# Blocky_Mini_Ultra.net
KiCad netlist of a schematic drawn in EAGLE
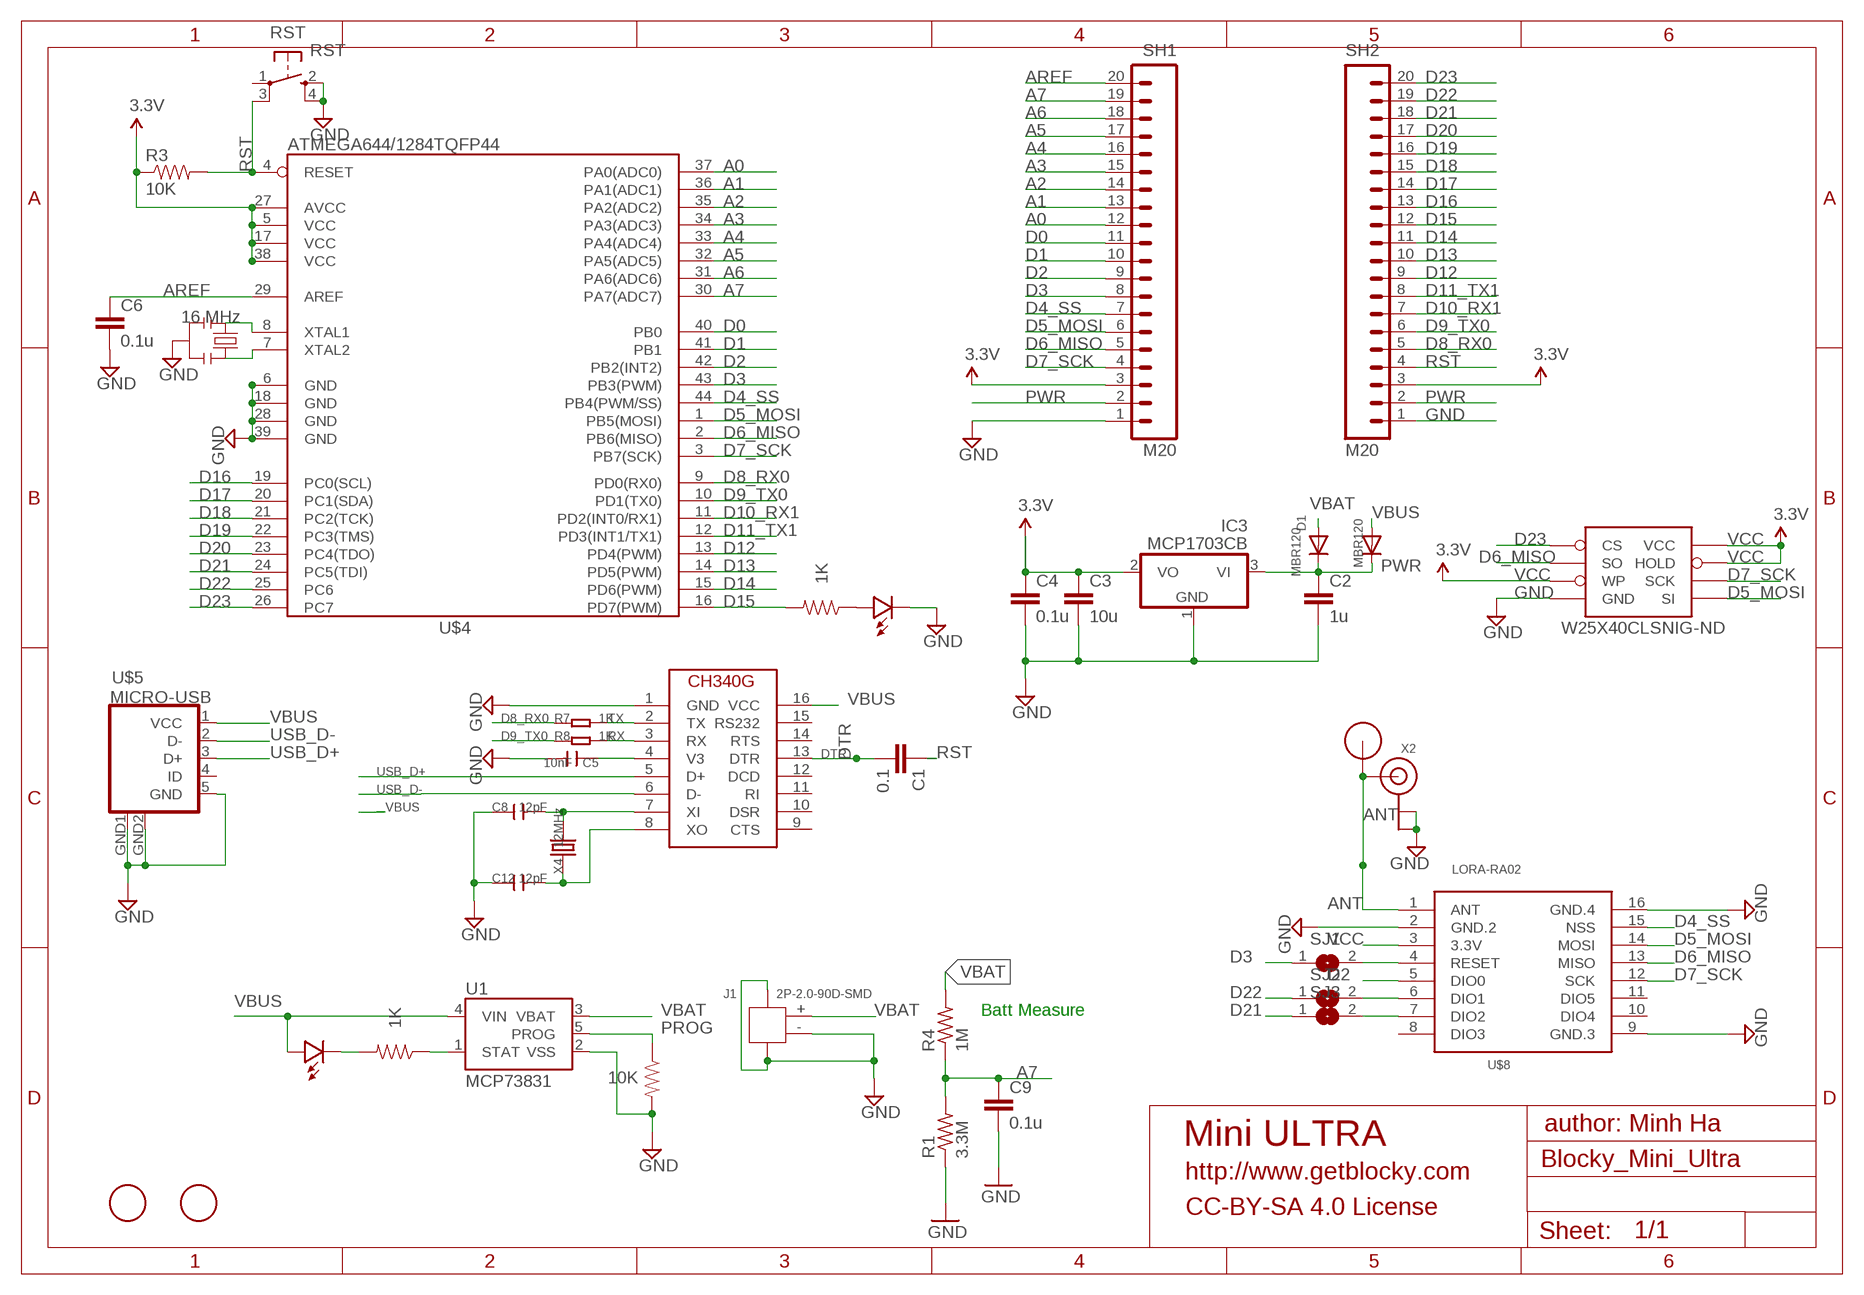
[diagram p0: schematic, sheet 1]

(export (version "E")
  (design (tool "Eeschema 10.0.6"))
  (components
    (comp (ref "C1")
      (value "0.1")
      (footprint "eagle-import:0603-CAP")
      (libsource (lib "eagle-import") (part "CAP0603-CAP"))
    )
    (comp (ref "C2")
      (value "1u")
      (footprint "eagle-import:0603-CAP")
      (libsource (lib "eagle-import") (part "CAP0603-CAP"))
    )
    (comp (ref "C3")
      (value "10u")
      (footprint "eagle-import:0603-CAP")
      (libsource (lib "eagle-import") (part "CAP0603-CAP"))
    )
    (comp (ref "C4")
      (value "0.1u")
      (footprint "eagle-import:0603-CAP")
      (libsource (lib "eagle-import") (part "CAP0603-CAP"))
    )
    (comp (ref "C5")
      (value "10nF")
      (footprint "eagle-import:C0603")
      (libsource (lib "eagle-import") (part "C-0603"))
    )
    (comp (ref "C6")
      (value "0.1u")
      (footprint "eagle-import:0603-CAP")
      (libsource (lib "eagle-import") (part "CAP0603-CAP"))
    )
    (comp (ref "C8")
      (value "12pF")
      (footprint "eagle-import:C0603")
      (libsource (lib "eagle-import") (part "C-0603"))
    )
    (comp (ref "C9")
      (value "0.1u")
      (footprint "eagle-import:0603-CAP")
      (libsource (lib "eagle-import") (part "CAP0603-CAP"))
    )
    (comp (ref "C12")
      (value "12pF")
      (footprint "eagle-import:C0603")
      (libsource (lib "eagle-import") (part "C-0603"))
    )
    (comp (ref "CHG")
      (value "RED")
      (footprint "eagle-import:0603-LED")
      (libsource (lib "eagle-import") (part "LED0603"))
    )
    (comp (ref "D1")
      (value "MBR120")
      (footprint "eagle-import:SOD-123")
      (libsource (lib "eagle-import") (part "DIODESOD-123"))
    )
    (comp (ref "IC3")
      (value "MCP1703CB")
      (footprint "eagle-import:SOT23")
      (libsource (lib "eagle-import") (part "MCP1703CB"))
    )
    (comp (ref "J1")
      (value "2P-2.0-90D-SMD")
      (footprint "eagle-import:HW2-SMD-2.0-90D")
      (libsource (lib "eagle-import") (part "CONN-HEADER-SMD-PH-SIDE-(2P-2.0MM)"))
    )
    (comp (ref "MBR0001")
      (value "MBR120")
      (footprint "eagle-import:SOD-123")
      (libsource (lib "eagle-import") (part "DIODESOD-123"))
    )
    (comp (ref "R1")
      (value "3.3M")
      (footprint "eagle-import:R0603")
      (libsource (lib "eagle-import") (part "R-US_R0603"))
    )
    (comp (ref "R2")
      (value "1K")
      (footprint "eagle-import:0603-RES")
      (libsource (lib "eagle-import") (part "RESISTOR0603-RES"))
    )
    (comp (ref "R3")
      (value "10K")
      (footprint "eagle-import:0603-RES")
      (libsource (lib "eagle-import") (part "RESISTOR0603-RES"))
    )
    (comp (ref "R4")
      (value "1M")
      (footprint "eagle-import:R0603")
      (libsource (lib "eagle-import") (part "R-US_R0603"))
    )
    (comp (ref "R5")
      (value "1K")
      (footprint "eagle-import:0603-RES")
      (libsource (lib "eagle-import") (part "RESISTOR0603-RES"))
    )
    (comp (ref "R6")
      (value "10K")
      (footprint "eagle-import:0603-RES")
      (libsource (lib "eagle-import") (part "RESISTOR0603-RES"))
    )
    (comp (ref "R7")
      (value "1K")
      (footprint "eagle-import:R0603")
      (libsource (lib "eagle-import") (part "R-0603"))
    )
    (comp (ref "R8")
      (value "1K")
      (footprint "eagle-import:R0603")
      (libsource (lib "eagle-import") (part "R-0603"))
    )
    (comp (ref "RST")
      (value "RST")
      (footprint "eagle-import:KMR2")
      (libsource (lib "eagle-import") (part "SPST_TACT-KMR2"))
    )
    (comp (ref "SH1")
      (value "M20")
      (footprint "eagle-import:1X20")
      (libsource (lib "eagle-import") (part "M20"))
    )
    (comp (ref "SH2")
      (value "M20")
      (footprint "eagle-import:1X20")
      (libsource (lib "eagle-import") (part "M20"))
    )
    (comp (ref "SJ1")
      (value "SOLDERJUMPER")
      (footprint "eagle-import:SOLDERJUMPER_ARROW_NOPASTE")
      (libsource (lib "eagle-import") (part "SOLDERJUMPER"))
    )
    (comp (ref "SJ2")
      (value "SOLDERJUMPER")
      (footprint "eagle-import:SOLDERJUMPER_ARROW_NOPASTE")
      (libsource (lib "eagle-import") (part "SOLDERJUMPER"))
    )
    (comp (ref "SJ3")
      (value "SOLDERJUMPER")
      (footprint "eagle-import:SOLDERJUMPER_ARROW_NOPASTE")
      (libsource (lib "eagle-import") (part "SOLDERJUMPER"))
    )
    (comp (ref "U$1")
      (value "RFM12B_ANTENNA")
      (footprint "eagle-import:RFM12B-ANTENNA")
      (libsource (lib "eagle-import") (part "RFM12B_ANTENNA"))
    )
    (comp (ref "U$2")
      (value "FIDUCIAL")
      (footprint "eagle-import:FIDUCIAL_1MM")
      (libsource (lib "eagle-import") (part "FIDUCIAL"))
    )
    (comp (ref "U$4")
      (value "ATMEGA644/1284TQFP44")
      (footprint "eagle-import:TQFP44")
      (libsource (lib "eagle-import") (part "ATMEGA644/1284TQFP44"))
    )
    (comp (ref "U$5")
      (value "MICRO-USB")
      (footprint "eagle-import:MICRO-USB")
      (libsource (lib "eagle-import") (part "MICRO-USB"))
    )
    (comp (ref "U$6")
      (value "LED0603")
      (footprint "eagle-import:0603-LED")
      (libsource (lib "eagle-import") (part "LED0603"))
    )
    (comp (ref "U$7")
      (value "FIDUCIAL")
      (footprint "eagle-import:FIDUCIAL_1MM")
      (libsource (lib "eagle-import") (part "FIDUCIAL"))
    )
    (comp (ref "U$8")
      (value "LORA-RA02")
      (footprint "eagle-import:LORA-RA2-SMD")
      (libsource (lib "eagle-import") (part "LORA-RA-02-433MHZ"))
    )
    (comp (ref "U$9")
      (value "CH340G")
      (footprint "eagle-import:SOIC16")
      (libsource (lib "eagle-import") (part "CH340G"))
    )
    (comp (ref "U1")
      (value "MCP73831")
      (footprint "eagle-import:SOT23-5")
      (libsource (lib "eagle-import") (part "MCP73831"))
    )
    (comp (ref "W25X40CLSNIG-ND")
      (value "AT25F512BWIDE_5.3MM")
      (footprint "eagle-import:SO08WIDE")
      (libsource (lib "eagle-import") (part "AT25F512BWIDE_5.3MM"))
    )
    (comp (ref "X1")
      (value "16 MHz")
      (footprint "eagle-import:RESONATOR-SMD")
      (libsource (lib "eagle-import") (part "RESONATORSMD"))
    )
    (comp (ref "X2")
      (value "ANTENNA_U.FL")
      (footprint "eagle-import:U.FL")
      (libsource (lib "eagle-import") (part "ANTENNA_U.FL"))
    )
    (comp (ref "X4")
      (value "12MHz")
      (footprint "eagle-import:2P-SMD-5X3.2")
      (libsource (lib "eagle-import") (part "CRYSTAL'5032'"))
    )
  )
  (nets
    (net (code "1") (name "/A0") (class "Default")
      (node (ref "SH1") (pin "12") (pinfunction "12_12") (pintype "passive"))
      (node (ref "U$4") (pin "37") (pinfunction "PA0(ADC0)_37") (pintype "bidirectional"))
    )
    (net (code "2") (name "/A1") (class "Default")
      (node (ref "SH1") (pin "13") (pinfunction "13_13") (pintype "passive"))
      (node (ref "U$4") (pin "36") (pinfunction "PA1(ADC1)_36") (pintype "bidirectional"))
    )
    (net (code "3") (name "/A2") (class "Default")
      (node (ref "SH1") (pin "14") (pinfunction "14_14") (pintype "passive"))
      (node (ref "U$4") (pin "35") (pinfunction "PA2(ADC2)_35") (pintype "bidirectional"))
    )
    (net (code "4") (name "/A3") (class "Default")
      (node (ref "SH1") (pin "15") (pinfunction "15_15") (pintype "passive"))
      (node (ref "U$4") (pin "34") (pinfunction "PA3(ADC3)_34") (pintype "bidirectional"))
    )
    (net (code "5") (name "/A4") (class "Default")
      (node (ref "SH1") (pin "16") (pinfunction "16_16") (pintype "passive"))
      (node (ref "U$4") (pin "33") (pinfunction "PA4(ADC4)_33") (pintype "bidirectional"))
    )
    (net (code "6") (name "/A5") (class "Default")
      (node (ref "SH1") (pin "17") (pinfunction "17_17") (pintype "passive"))
      (node (ref "U$4") (pin "32") (pinfunction "PA5(ADC5)_32") (pintype "bidirectional"))
    )
    (net (code "7") (name "/A6") (class "Default")
      (node (ref "SH1") (pin "18") (pinfunction "18_18") (pintype "passive"))
      (node (ref "U$4") (pin "31") (pinfunction "PA6(ADC6)_31") (pintype "bidirectional"))
    )
    (net (code "8") (name "/A7") (class "Default")
      (node (ref "C9") (pin "1") (pinfunction "1_1") (pintype "passive"))
      (node (ref "R1") (pin "2") (pinfunction "2_2") (pintype "passive"))
      (node (ref "R4") (pin "1") (pinfunction "1_1") (pintype "passive"))
      (node (ref "SH1") (pin "19") (pinfunction "19_19") (pintype "passive"))
      (node (ref "U$4") (pin "30") (pinfunction "PA7(ADC7)_30") (pintype "bidirectional"))
    )
    (net (code "9") (name "/ANT") (class "Default")
      (node (ref "U$1") (pin "P$1") (pinfunction "1_P$1") (pintype "bidirectional"))
      (node (ref "U$8") (pin "1") (pinfunction "ANT_1") (pintype "bidirectional"))
      (node (ref "X2") (pin "3") (pinfunction "SIGNAL_3") (pintype "passive"))
    )
    (net (code "10") (name "/AREF") (class "Default")
      (node (ref "C6") (pin "1") (pinfunction "1_1") (pintype "passive"))
      (node (ref "SH1") (pin "20") (pinfunction "20_20") (pintype "passive"))
      (node (ref "U$4") (pin "29") (pinfunction "AREF_29") (pintype "bidirectional"))
    )
    (net (code "11") (name "/D0") (class "Default")
      (node (ref "SH1") (pin "11") (pinfunction "11_11") (pintype "passive"))
      (node (ref "U$4") (pin "40") (pinfunction "PB0_40") (pintype "bidirectional"))
    )
    (net (code "12") (name "/D1") (class "Default")
      (node (ref "SH1") (pin "10") (pinfunction "10_10") (pintype "passive"))
      (node (ref "U$4") (pin "41") (pinfunction "PB1_41") (pintype "bidirectional"))
    )
    (net (code "13") (name "/D2") (class "Default")
      (node (ref "SH1") (pin "9") (pinfunction "9_9") (pintype "passive"))
      (node (ref "U$4") (pin "42") (pinfunction "PB2(INT2)_42") (pintype "bidirectional"))
      (node (ref "U$8") (pin "5") (pinfunction "DIO0_5") (pintype "bidirectional"))
    )
    (net (code "14") (name "/D3") (class "Default")
      (node (ref "SH1") (pin "8") (pinfunction "8_8") (pintype "passive"))
      (node (ref "SJ1") (pin "1") (pinfunction "1_1") (pintype "passive"))
      (node (ref "U$4") (pin "43") (pinfunction "PB3(PWM)_43") (pintype "bidirectional"))
    )
    (net (code "15") (name "/D4_SS") (class "Default")
      (node (ref "SH1") (pin "7") (pinfunction "7_7") (pintype "passive"))
      (node (ref "U$4") (pin "44") (pinfunction "PB4(PWM/SS)_44") (pintype "bidirectional"))
      (node (ref "U$8") (pin "15") (pinfunction "NSS_15") (pintype "bidirectional"))
    )
    (net (code "16") (name "/D5_MOSI") (class "Default")
      (node (ref "SH1") (pin "6") (pinfunction "6_6") (pintype "passive"))
      (node (ref "U$4") (pin "1") (pinfunction "PB5(MOSI)_1") (pintype "bidirectional"))
      (node (ref "U$8") (pin "14") (pinfunction "MOSI_14") (pintype "bidirectional"))
      (node (ref "W25X40CLSNIG-ND") (pin "5") (pinfunction "SI_5") (pintype "bidirectional"))
    )
    (net (code "17") (name "/D6_MISO") (class "Default")
      (node (ref "SH1") (pin "5") (pinfunction "5_5") (pintype "passive"))
      (node (ref "U$4") (pin "2") (pinfunction "PB6(MISO)_2") (pintype "bidirectional"))
      (node (ref "U$8") (pin "13") (pinfunction "MISO_13") (pintype "bidirectional"))
      (node (ref "W25X40CLSNIG-ND") (pin "2") (pinfunction "SO_2") (pintype "bidirectional"))
    )
    (net (code "18") (name "/D7_SCK") (class "Default")
      (node (ref "SH1") (pin "4") (pinfunction "4_4") (pintype "passive"))
      (node (ref "U$4") (pin "3") (pinfunction "PB7(SCK)_3") (pintype "bidirectional"))
      (node (ref "U$8") (pin "12") (pinfunction "SCK_12") (pintype "bidirectional"))
      (node (ref "W25X40CLSNIG-ND") (pin "6") (pinfunction "SCK_6") (pintype "bidirectional"))
    )
    (net (code "19") (name "/D8_RX0") (class "Default")
      (node (ref "R7") (pin "1") (pinfunction "1_1") (pintype "passive"))
      (node (ref "SH2") (pin "5") (pinfunction "5_5") (pintype "passive"))
      (node (ref "U$4") (pin "9") (pinfunction "PD0(RX0)_9") (pintype "bidirectional"))
    )
    (net (code "20") (name "/D9_TX0") (class "Default")
      (node (ref "R8") (pin "1") (pinfunction "1_1") (pintype "passive"))
      (node (ref "SH2") (pin "6") (pinfunction "6_6") (pintype "passive"))
      (node (ref "U$4") (pin "10") (pinfunction "PD1(TX0)_10") (pintype "bidirectional"))
    )
    (net (code "21") (name "/D10_RX1") (class "Default")
      (node (ref "SH2") (pin "7") (pinfunction "7_7") (pintype "passive"))
      (node (ref "U$4") (pin "11") (pinfunction "PD2(INT0/RX1)_11") (pintype "bidirectional"))
    )
    (net (code "22") (name "/D11_TX1") (class "Default")
      (node (ref "SH2") (pin "8") (pinfunction "8_8") (pintype "passive"))
      (node (ref "U$4") (pin "12") (pinfunction "PD3(INT1/TX1)_12") (pintype "bidirectional"))
    )
    (net (code "23") (name "/D12") (class "Default")
      (node (ref "SH2") (pin "9") (pinfunction "9_9") (pintype "passive"))
      (node (ref "U$4") (pin "13") (pinfunction "PD4(PWM)_13") (pintype "bidirectional"))
    )
    (net (code "24") (name "/D13") (class "Default")
      (node (ref "SH2") (pin "10") (pinfunction "10_10") (pintype "passive"))
      (node (ref "U$4") (pin "14") (pinfunction "PD5(PWM)_14") (pintype "bidirectional"))
    )
    (net (code "25") (name "/D14") (class "Default")
      (node (ref "SH2") (pin "11") (pinfunction "11_11") (pintype "passive"))
      (node (ref "U$4") (pin "15") (pinfunction "PD6(PWM)_15") (pintype "bidirectional"))
    )
    (net (code "26") (name "/D15") (class "Default")
      (node (ref "R2") (pin "2") (pinfunction "2_2") (pintype "passive"))
      (node (ref "SH2") (pin "12") (pinfunction "12_12") (pintype "passive"))
      (node (ref "U$4") (pin "16") (pinfunction "PD7(PWM)_16") (pintype "bidirectional"))
    )
    (net (code "27") (name "/D16") (class "Default")
      (node (ref "SH2") (pin "13") (pinfunction "13_13") (pintype "passive"))
      (node (ref "U$4") (pin "19") (pinfunction "PC0(SCL)_19") (pintype "bidirectional"))
    )
    (net (code "28") (name "/D17") (class "Default")
      (node (ref "SH2") (pin "14") (pinfunction "14_14") (pintype "passive"))
      (node (ref "U$4") (pin "20") (pinfunction "PC1(SDA)_20") (pintype "bidirectional"))
    )
    (net (code "29") (name "/D18") (class "Default")
      (node (ref "SH2") (pin "15") (pinfunction "15_15") (pintype "passive"))
      (node (ref "U$4") (pin "21") (pinfunction "PC2(TCK)_21") (pintype "bidirectional"))
    )
    (net (code "30") (name "/D19") (class "Default")
      (node (ref "SH2") (pin "16") (pinfunction "16_16") (pintype "passive"))
      (node (ref "U$4") (pin "22") (pinfunction "PC3(TMS)_22") (pintype "bidirectional"))
    )
    (net (code "31") (name "/D20") (class "Default")
      (node (ref "SH2") (pin "17") (pinfunction "17_17") (pintype "passive"))
      (node (ref "U$4") (pin "23") (pinfunction "PC4(TDO)_23") (pintype "bidirectional"))
    )
    (net (code "32") (name "/D21") (class "Default")
      (node (ref "SH2") (pin "18") (pinfunction "18_18") (pintype "passive"))
      (node (ref "SJ3") (pin "1") (pinfunction "1_1") (pintype "passive"))
      (node (ref "U$4") (pin "24") (pinfunction "PC5(TDI)_24") (pintype "bidirectional"))
    )
    (net (code "33") (name "/D22") (class "Default")
      (node (ref "SH2") (pin "19") (pinfunction "19_19") (pintype "passive"))
      (node (ref "SJ2") (pin "1") (pinfunction "1_1") (pintype "passive"))
      (node (ref "U$4") (pin "25") (pinfunction "PC6_25") (pintype "bidirectional"))
    )
    (net (code "34") (name "/D23") (class "Default")
      (node (ref "SH2") (pin "20") (pinfunction "20_20") (pintype "passive"))
      (node (ref "U$4") (pin "26") (pinfunction "PC7_26") (pintype "bidirectional"))
      (node (ref "W25X40CLSNIG-ND") (pin "1") (pinfunction "CS_1") (pintype "bidirectional"))
    )
    (net (code "35") (name "/DTR") (class "Default")
      (node (ref "C1") (pin "2") (pinfunction "2_2") (pintype "passive"))
      (node (ref "U$9") (pin "13") (pinfunction "DTR_13") (pintype "bidirectional"))
    )
    (net (code "36") (name "/PROG") (class "Default")
      (node (ref "R6") (pin "1") (pinfunction "1_1") (pintype "passive"))
      (node (ref "U1") (pin "5") (pinfunction "PROG_5") (pintype "input"))
    )
    (net (code "37") (name "/PWR") (class "Default")
      (node (ref "C2") (pin "1") (pinfunction "1_1") (pintype "passive"))
      (node (ref "D1") (pin "C") (pinfunction "C_C") (pintype "passive"))
      (node (ref "IC3") (pin "3") (pinfunction "VI_3") (pintype "input"))
      (node (ref "MBR0001") (pin "C") (pinfunction "C_C") (pintype "passive"))
      (node (ref "SH1") (pin "2") (pinfunction "2_2") (pintype "passive"))
      (node (ref "SH2") (pin "2") (pinfunction "2_2") (pintype "passive"))
    )
    (net (code "38") (name "/RST") (class "Default")
      (node (ref "C1") (pin "1") (pinfunction "1_1") (pintype "passive"))
      (node (ref "R3") (pin "2") (pinfunction "2_2") (pintype "passive"))
      (node (ref "RST") (pin "3") (pinfunction "P1_3") (pintype "passive"))
      (node (ref "SH2") (pin "4") (pinfunction "4_4") (pintype "passive"))
      (node (ref "U$4") (pin "4") (pinfunction "RESET_4") (pintype "bidirectional"))
    )
    (net (code "39") (name "/RX") (class "Default")
      (node (ref "R8") (pin "2") (pinfunction "2_2") (pintype "passive"))
      (node (ref "U$9") (pin "3") (pinfunction "RX_3") (pintype "bidirectional"))
    )
    (net (code "40") (name "/TX") (class "Default")
      (node (ref "R7") (pin "2") (pinfunction "2_2") (pintype "passive"))
      (node (ref "U$9") (pin "2") (pinfunction "TX_2") (pintype "bidirectional"))
    )
    (net (code "41") (name "/USB_D+") (class "Default")
      (node (ref "U$5") (pin "3") (pinfunction "D+_3") (pintype "bidirectional"))
      (node (ref "U$9") (pin "5") (pinfunction "D+_5") (pintype "bidirectional"))
    )
    (net (code "42") (name "/USB_D-") (class "Default")
      (node (ref "U$5") (pin "2") (pinfunction "D-_2") (pintype "bidirectional"))
      (node (ref "U$9") (pin "6") (pinfunction "D-_6") (pintype "bidirectional"))
    )
    (net (code "43") (name "/VBUS") (class "Default")
      (node (ref "CHG") (pin "PLUS") (pinfunction "PLUS_PLUS") (pintype "passive"))
      (node (ref "MBR0001") (pin "A") (pinfunction "A_A") (pintype "passive"))
      (node (ref "U$5") (pin "1") (pinfunction "VCC_1") (pintype "power_in"))
      (node (ref "U$9") (pin "16") (pinfunction "VCC_16") (pintype "bidirectional"))
      (node (ref "U1") (pin "4") (pinfunction "VIN_4") (pintype "power_in"))
    )
    (net (code "44") (name "3.3V") (class "Default")
      (node (ref "C3") (pin "1") (pinfunction "1_1") (pintype "passive"))
      (node (ref "C4") (pin "1") (pinfunction "1_1") (pintype "passive"))
      (node (ref "IC3") (pin "2") (pinfunction "VO_2") (pintype "passive"))
      (node (ref "R3") (pin "1") (pinfunction "1_1") (pintype "passive"))
      (node (ref "SH1") (pin "3") (pinfunction "3_3") (pintype "passive"))
      (node (ref "SH2") (pin "3") (pinfunction "3_3") (pintype "passive"))
      (node (ref "U$4") (pin "17") (pinfunction "VCC_17") (pintype "bidirectional"))
      (node (ref "U$4") (pin "27") (pinfunction "AVCC_27") (pintype "bidirectional"))
      (node (ref "U$4") (pin "38") (pinfunction "VCC_38") (pintype "bidirectional"))
      (node (ref "U$4") (pin "5") (pinfunction "VCC_5") (pintype "bidirectional"))
      (node (ref "U$8") (pin "3") (pinfunction "3.3V_3") (pintype "power_in"))
      (node (ref "W25X40CLSNIG-ND") (pin "3") (pinfunction "WP_3") (pintype "bidirectional"))
      (node (ref "W25X40CLSNIG-ND") (pin "7") (pinfunction "HOLD_7") (pintype "bidirectional"))
      (node (ref "W25X40CLSNIG-ND") (pin "8") (pinfunction "VCC_8") (pintype "bidirectional"))
    )
    (net (code "45") (name "GND") (class "Default")
      (node (ref "C12") (pin "1") (pinfunction "1_1") (pintype "passive"))
      (node (ref "C2") (pin "2") (pinfunction "2_2") (pintype "passive"))
      (node (ref "C3") (pin "2") (pinfunction "2_2") (pintype "passive"))
      (node (ref "C4") (pin "2") (pinfunction "2_2") (pintype "passive"))
      (node (ref "C5") (pin "2") (pinfunction "2_2") (pintype "passive"))
      (node (ref "C6") (pin "2") (pinfunction "2_2") (pintype "passive"))
      (node (ref "C8") (pin "1") (pinfunction "1_1") (pintype "passive"))
      (node (ref "C9") (pin "2") (pinfunction "2_2") (pintype "passive"))
      (node (ref "IC3") (pin "1") (pinfunction "GND_1") (pintype "passive"))
      (node (ref "J1") (pin "-") (pinfunction "2_-") (pintype "bidirectional"))
      (node (ref "J1") (pin "3") (pinfunction "3_3") (pintype "bidirectional"))
      (node (ref "J1") (pin "4") (pinfunction "4_4") (pintype "bidirectional"))
      (node (ref "R1") (pin "1") (pinfunction "1_1") (pintype "passive"))
      (node (ref "R6") (pin "2") (pinfunction "2_2") (pintype "passive"))
      (node (ref "RST") (pin "2") (pinfunction "S_2") (pintype "passive"))
      (node (ref "RST") (pin "4") (pinfunction "S1_4") (pintype "passive"))
      (node (ref "SH1") (pin "1") (pinfunction "1_1") (pintype "passive"))
      (node (ref "SH2") (pin "1") (pinfunction "1_1") (pintype "passive"))
      (node (ref "U$4") (pin "18") (pinfunction "GND_18") (pintype "bidirectional"))
      (node (ref "U$4") (pin "28") (pinfunction "GND_28") (pintype "bidirectional"))
      (node (ref "U$4") (pin "39") (pinfunction "GND_39") (pintype "bidirectional"))
      (node (ref "U$4") (pin "6") (pinfunction "GND_6") (pintype "bidirectional"))
      (node (ref "U$5") (pin "5") (pinfunction "GND_5") (pintype "power_in"))
      (node (ref "U$5") (pin "GND1") (pinfunction "GND_GND1") (pintype "power_in"))
      (node (ref "U$5") (pin "GND2") (pinfunction "GND_GND2") (pintype "power_in"))
      (node (ref "U$6") (pin "MINUS") (pinfunction "MINUS_MINUS") (pintype "passive"))
      (node (ref "U$8") (pin "16") (pinfunction "GND.4_16") (pintype "power_in"))
      (node (ref "U$8") (pin "2") (pinfunction "GND.2_2") (pintype "power_in"))
      (node (ref "U$8") (pin "9") (pinfunction "GND.3_9") (pintype "power_in"))
      (node (ref "U$9") (pin "1") (pinfunction "GND_1") (pintype "bidirectional"))
      (node (ref "U1") (pin "2") (pinfunction "VSS_2") (pintype "power_in"))
      (node (ref "W25X40CLSNIG-ND") (pin "4") (pinfunction "GND_4") (pintype "bidirectional"))
      (node (ref "X1") (pin "2") (pinfunction "2_2") (pintype "passive"))
      (node (ref "X2") (pin "1") (pinfunction "GND_1") (pintype "passive"))
      (node (ref "X2") (pin "2") (pinfunction "GND_2") (pintype "passive"))
    )
    (net (code "46") (name "Net-(CHG-PadMINUS)") (class "Default")
      (node (ref "CHG") (pin "MINUS") (pinfunction "MINUS_MINUS") (pintype "passive"))
      (node (ref "R5") (pin "2") (pinfunction "2_2") (pintype "passive"))
    )
    (net (code "47") (name "Net-(R2-Pad1)") (class "Default")
      (node (ref "R2") (pin "1") (pinfunction "1_1") (pintype "passive"))
      (node (ref "U$6") (pin "PLUS") (pinfunction "PLUS_PLUS") (pintype "passive"))
    )
    (net (code "48") (name "Net-(U$4-XTAL1)") (class "Default")
      (node (ref "U$4") (pin "8") (pinfunction "XTAL1_8") (pintype "bidirectional"))
      (node (ref "X1") (pin "1") (pinfunction "1_1") (pintype "passive"))
    )
    (net (code "49") (name "Net-(U$4-XTAL2)") (class "Default")
      (node (ref "U$4") (pin "7") (pinfunction "XTAL2_7") (pintype "bidirectional"))
      (node (ref "X1") (pin "3") (pinfunction "3_3") (pintype "passive"))
    )
    (net (code "50") (name "Net-(U$8-DIO1)") (class "Default")
      (node (ref "SJ2") (pin "2") (pinfunction "2_2") (pintype "passive"))
      (node (ref "U$8") (pin "6") (pinfunction "DIO1_6") (pintype "bidirectional"))
    )
    (net (code "51") (name "Net-(U$8-DIO2)") (class "Default")
      (node (ref "SJ3") (pin "2") (pinfunction "2_2") (pintype "passive"))
      (node (ref "U$8") (pin "7") (pinfunction "DIO2_7") (pintype "bidirectional"))
    )
    (net (code "52") (name "Net-(U$8-RESET)") (class "Default")
      (node (ref "SJ1") (pin "2") (pinfunction "2_2") (pintype "passive"))
      (node (ref "U$8") (pin "4") (pinfunction "RESET_4") (pintype "bidirectional"))
    )
    (net (code "53") (name "Net-(U$9-V3)") (class "Default")
      (node (ref "C5") (pin "1") (pinfunction "1_1") (pintype "passive"))
      (node (ref "U$9") (pin "4") (pinfunction "V3_4") (pintype "bidirectional"))
    )
    (net (code "54") (name "Net-(U$9-XI)") (class "Default")
      (node (ref "C8") (pin "2") (pinfunction "2_2") (pintype "passive"))
      (node (ref "U$9") (pin "7") (pinfunction "XI_7") (pintype "bidirectional"))
      (node (ref "X4") (pin "2") (pinfunction "2_2") (pintype "passive"))
    )
    (net (code "55") (name "Net-(U$9-XO)") (class "Default")
      (node (ref "C12") (pin "2") (pinfunction "2_2") (pintype "passive"))
      (node (ref "U$9") (pin "8") (pinfunction "XO_8") (pintype "bidirectional"))
      (node (ref "X4") (pin "1") (pinfunction "1_1") (pintype "passive"))
    )
    (net (code "56") (name "Net-(U1-STAT)") (class "Default")
      (node (ref "R5") (pin "1") (pinfunction "1_1") (pintype "passive"))
      (node (ref "U1") (pin "1") (pinfunction "STAT_1") (pintype "output"))
    )
    (net (code "57") (name "VBAT") (class "Default")
      (node (ref "D1") (pin "A") (pinfunction "A_A") (pintype "passive"))
      (node (ref "J1") (pin "+") (pinfunction "1_+") (pintype "bidirectional"))
      (node (ref "R4") (pin "2") (pinfunction "2_2") (pintype "passive"))
      (node (ref "U1") (pin "3") (pinfunction "VBAT_3") (pintype "power_in"))
    )
    (net (code "58") (name "unconnected-(RST-P-Pad1)") (class "Default")
      (node (ref "RST") (pin "1") (pinfunction "P_1") (pintype "passive"))
    )
    (net (code "59") (name "unconnected-(U$5-ID-Pad4)") (class "Default")
      (node (ref "U$5") (pin "4") (pinfunction "ID_4") (pintype "bidirectional"))
    )
    (net (code "60") (name "unconnected-(U$8-DIO3-Pad8)") (class "Default")
      (node (ref "U$8") (pin "8") (pinfunction "DIO3_8") (pintype "bidirectional"))
    )
    (net (code "61") (name "unconnected-(U$8-DIO4-Pad10)") (class "Default")
      (node (ref "U$8") (pin "10") (pinfunction "DIO4_10") (pintype "bidirectional"))
    )
    (net (code "62") (name "unconnected-(U$8-DIO5-Pad11)") (class "Default")
      (node (ref "U$8") (pin "11") (pinfunction "DIO5_11") (pintype "bidirectional"))
    )
    (net (code "63") (name "unconnected-(U$9-CTS-Pad9)") (class "Default")
      (node (ref "U$9") (pin "9") (pinfunction "CTS_9") (pintype "bidirectional"))
    )
    (net (code "64") (name "unconnected-(U$9-DCD-Pad12)") (class "Default")
      (node (ref "U$9") (pin "12") (pinfunction "DCD_12") (pintype "bidirectional"))
    )
    (net (code "65") (name "unconnected-(U$9-DSR-Pad10)") (class "Default")
      (node (ref "U$9") (pin "10") (pinfunction "DSR_10") (pintype "bidirectional"))
    )
    (net (code "66") (name "unconnected-(U$9-RI-Pad11)") (class "Default")
      (node (ref "U$9") (pin "11") (pinfunction "RI_11") (pintype "bidirectional"))
    )
    (net (code "67") (name "unconnected-(U$9-RS232-Pad15)") (class "Default")
      (node (ref "U$9") (pin "15") (pinfunction "RS232_15") (pintype "bidirectional"))
    )
    (net (code "68") (name "unconnected-(U$9-RTS-Pad14)") (class "Default")
      (node (ref "U$9") (pin "14") (pinfunction "RTS_14") (pintype "bidirectional"))
    )
  )
)
